# 1-Controller.net
KiCad netlist of a schematic drawn in Altium Designer
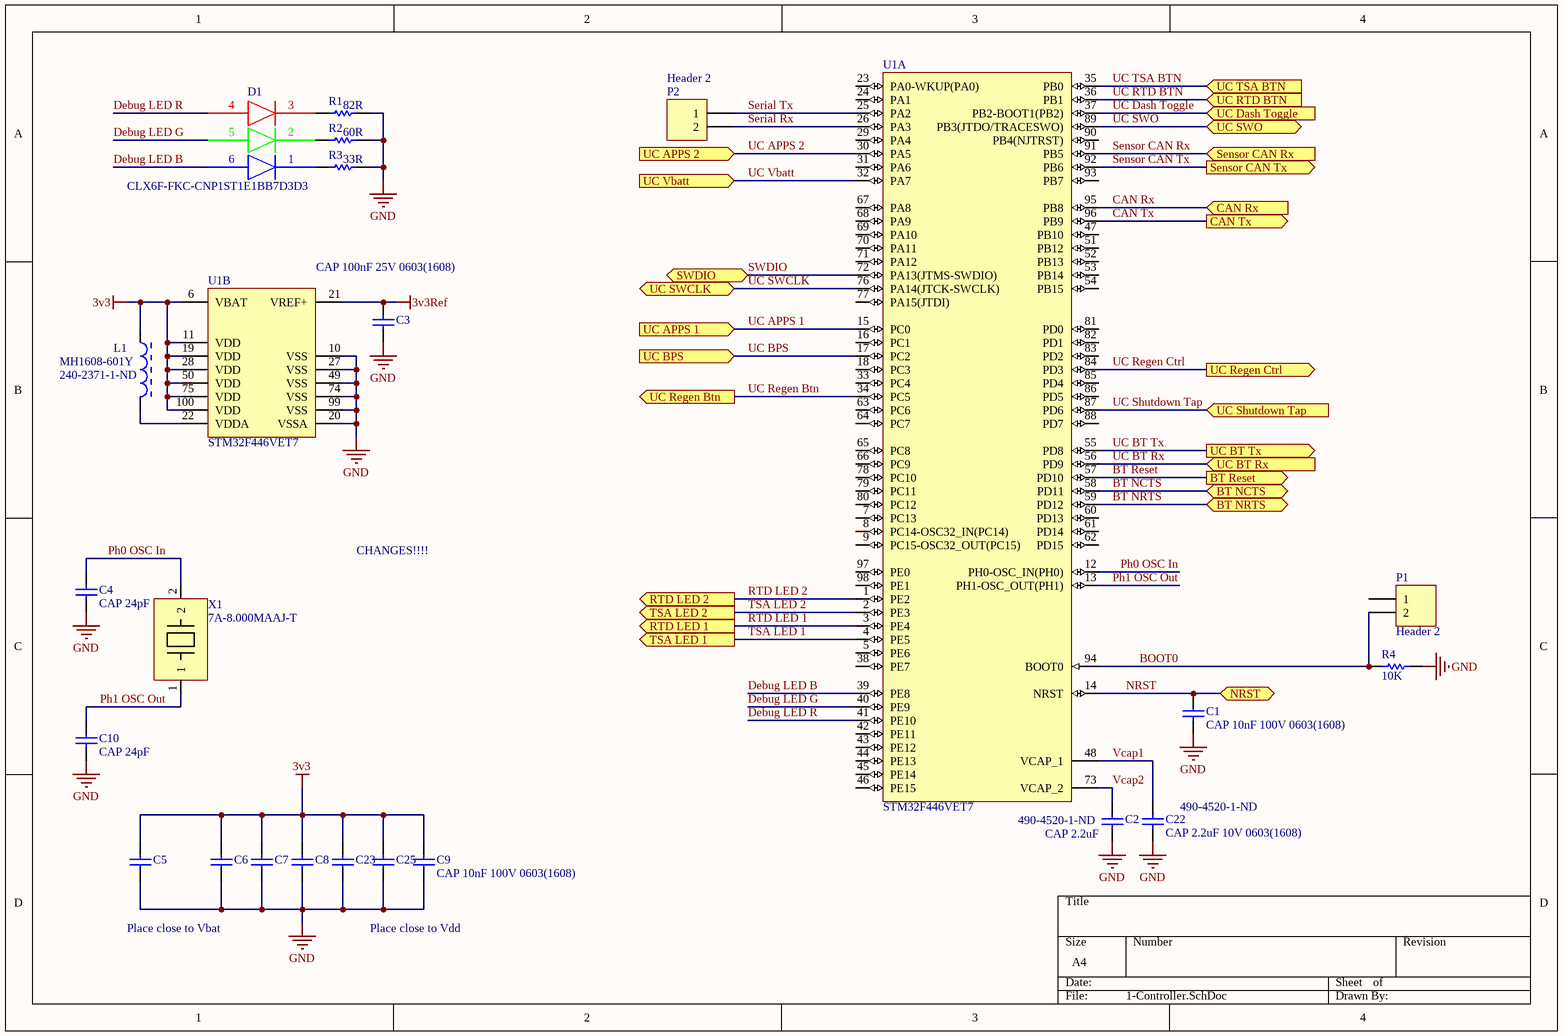
[diagram p0: 1-Controller.SchDoc]

(export (version "E")
  (design (tool "Eeschema 10.0.6"))
  (components
    (comp (ref "C1")
      (value "CAP 10nF 100V 0603(1608)")
      (footprint "CAPC0603(1608)100_M")
      (description "CAP 10nF 100V ±20% 0603 (1608 Metric) Thickness 1mm SMD")
      (fields (field (name "TOLERANCE") "Â±20%"))
      (libsource (lib "Altium Content Vault") (part "CAP"))
    )
    (comp (ref "C2")
      (value "CAP 2.2uF")
      (footprint "CAPC0603(1608)55_N")
      (description "CAP 2.2uF 10V ±10% 0603 (1608 Metric) Thickness 0.55mm SMD")
      (fields (field (name "TOLERANCE") "Â±10%") (field (name "SUPPLIER PART NUMBER 1") "490-4520-1-ND"))
      (libsource (lib "Altium Content Vault") (part "CAP"))
    )
    (comp (ref "C3")
      (value "CAP 100nF 25V 0603(1608)")
      (footprint "CAPC0603(1608)100_N")
      (description "CAP 100nF 25V ±20% 0603 (1608 Metric) Thickness 1mm SMD")
      (fields (field (name "TOLERANCE") "Â±20%"))
      (libsource (lib "Altium Content Vault") (part "CAP"))
    )
    (comp (ref "C4")
      (value "CAP 24pF")
      (footprint "CAPC0603(1608)100_N")
      (description "CAP 24pF 16V ±2% 0603 (1608 Metric) Thickness 1mm SMD")
      (fields (field (name "TOLERANCE") "Â±2%"))
      (libsource (lib "Altium Content Vault") (part "CAP"))
    )
    (comp (ref "C5")
      (value "CAP 10nF 100V 0603(1608)")
      (footprint "CAPC0603(1608)100_M")
      (description "CAP 10nF 100V ±20% 0603 (1608 Metric) Thickness 1mm SMD")
      (fields (field (name "TOLERANCE") "Â±20%"))
      (libsource (lib "Altium Content Vault") (part "CAP"))
    )
    (comp (ref "C6")
      (value "CAP 10nF 100V 0603(1608)")
      (footprint "CAPC0603(1608)100_M")
      (description "CAP 10nF 100V ±20% 0603 (1608 Metric) Thickness 1mm SMD")
      (fields (field (name "TOLERANCE") "Â±20%"))
      (libsource (lib "Altium Content Vault") (part "CAP"))
    )
    (comp (ref "C7")
      (value "CAP 10nF 100V 0603(1608)")
      (footprint "CAPC0603(1608)100_M")
      (description "CAP 10nF 100V ±20% 0603 (1608 Metric) Thickness 1mm SMD")
      (fields (field (name "TOLERANCE") "Â±20%"))
      (libsource (lib "Altium Content Vault") (part "CAP"))
    )
    (comp (ref "C8")
      (value "CAP 10nF 100V 0603(1608)")
      (footprint "CAPC0603(1608)100_M")
      (description "CAP 10nF 100V ±20% 0603 (1608 Metric) Thickness 1mm SMD")
      (fields (field (name "TOLERANCE") "Â±20%"))
      (libsource (lib "Altium Content Vault") (part "CAP"))
    )
    (comp (ref "C9")
      (value "CAP 10nF 100V 0603(1608)")
      (footprint "CAPC0603(1608)100_M")
      (description "CAP 10nF 100V ±20% 0603 (1608 Metric) Thickness 1mm SMD")
      (fields (field (name "TOLERANCE") "Â±20%"))
      (libsource (lib "Altium Content Vault") (part "CAP"))
    )
    (comp (ref "C10")
      (value "CAP 24pF")
      (footprint "CAPC0603(1608)100_N")
      (description "CAP 24pF 16V ±2% 0603 (1608 Metric) Thickness 1mm SMD")
      (fields (field (name "TOLERANCE") "Â±2%"))
      (libsource (lib "Altium Content Vault") (part "CAP"))
    )
    (comp (ref "C22")
      (value "CAP 2.2uF 10V 0603(1608)")
      (footprint "CAPC0603(1608)55_N")
      (description "CAP 2.2uF 10V ±10% 0603 (1608 Metric) Thickness 0.55mm SMD")
      (fields (field (name "TOLERANCE") "Â±10%") (field (name "SUPPLIER PART NUMBER 1") "490-4520-1-ND"))
      (libsource (lib "Altium Content Vault") (part "CAP"))
    )
    (comp (ref "C23")
      (value "CAP 10nF 100V 0603(1608)")
      (footprint "CAPC0603(1608)100_M")
      (description "CAP 10nF 100V ±20% 0603 (1608 Metric) Thickness 1mm SMD")
      (fields (field (name "TOLERANCE") "Â±20%"))
      (libsource (lib "Altium Content Vault") (part "CAP"))
    )
    (comp (ref "C25")
      (value "CAP 10nF 100V 0603(1608)")
      (footprint "CAPC0603(1608)100_M")
      (description "CAP 10nF 100V ±20% 0603 (1608 Metric) Thickness 1mm SMD")
      (fields (field (name "TOLERANCE") "Â±20%"))
      (libsource (lib "Altium Content Vault") (part "CAP"))
    )
    (comp (ref "D1")
      (value "CLX6F-FKC-CNP1ST1E1BB7D3D3")
      (footprint "CLX6C-FKB")
      (libsource (lib "VCB_2019") (part "LED - CLX6F-FKC-CNP1ST1E1BB7D3D3"))
    )
    (comp (ref "L1")
      (value "MH1608-601Y")
      (footprint "BOUR-MH1608_V")
      (description "Chip Bead, 600 Ohm, 1 A, -55 to 125 degC, 2-Pin SMD (0603), RoHS, Tape and Reel")
      (fields (field (name "MANUFACTURER") "Bourns") (field (name "SUPPLIER PART NUMBER 1") "240-2371-1-ND"))
      (libsource (lib "Altium Content Vault") (part "IND-FB-2"))
    )
    (comp (ref "P1")
      (value "Header 2")
      (footprint "HDR1X2")
      (description "Header, 2-Pin")
      (fields (field (name "PUBLISHER") "Altium Limited"))
      (libsource (lib "Miscellaneous Connectors") (part "Header 2"))
    )
    (comp (ref "P2")
      (value "Header 2")
      (footprint "HDR1X2")
      (description "Header, 2-Pin")
      (fields (field (name "PUBLISHER") "Altium Limited"))
      (libsource (lib "") (part "Header 2_1"))
    )
    (comp (ref "R1")
      (value "82R")
      (footprint "RESC0603(1608)_N")
      (description "82R 0.1W 5% 0603 (1608 Metric)  SMD")
      (fields (field (name "TOLERANCE") "5 %") (field (name "POWER") "0.1 W"))
      (libsource (lib "Altium Content Vault") (part "RES"))
    )
    (comp (ref "R2")
      (value "60R")
      (footprint "RESC0603(1608)_N")
      (description "60R4 0.1W 1% 0603 (1608 Metric)  SMD")
      (fields (field (name "TOLERANCE") "1 %") (field (name "POWER") "0.1 W"))
      (libsource (lib "Altium Content Vault") (part "RES"))
    )
    (comp (ref "R3")
      (value "33R")
      (footprint "RESC0603(1608)_N")
      (description "33R 0.1W 5% 0603 (1608 Metric)  SMD")
      (fields (field (name "TOLERANCE") "5 %") (field (name "POWER") "0.1 W"))
      (libsource (lib "Altium Content Vault") (part "RES"))
    )
    (comp (ref "R4")
      (value "10K")
      (footprint "RESC0603(1608)_N")
      (description "10K 0.1W 5% 0603 (1608 Metric)  SMD")
      (fields (field (name "TOLERANCE") "5 %") (field (name "POWER") "0.1 W"))
      (libsource (lib "Altium Content Vault") (part "RES"))
    )
    (comp (ref "U1")
      (value "STM32F446VET7")
      (footprint "STM-LQFP100_L")
      (libsource (lib "Altium Content Vault") (part "MC-ARM-STM32F446-LQFP100"))
    )
    (comp (ref "X1")
      (value "7A-8.000MAAJ-T")
      (footprint "2-SMD, No Lead")
      (fields (field (name "MANUFACTURER") "TXC CORPORATION"))
      (libsource (lib "VCU Library") (part "8MHz crystal, 7A-8.000MAAJ-T"))
    )
  )
  (nets
    (net (code "1") (name "/BOOT0") (class "Default")
      (node (ref "P1") (pin "2") (pinfunction "2_2") (pintype "passive"))
      (node (ref "R4") (pin "1") (pinfunction "1_1") (pintype "passive"))
      (node (ref "U1") (pin "94") (pinfunction "BOOT0_94") (pintype "input"))
    )
    (net (code "2") (name "/BT NCTS") (class "Default")
      (node (ref "U1") (pin "58") (pinfunction "PD11_58") (pintype "bidirectional"))
    )
    (net (code "3") (name "/BT NRTS") (class "Default")
      (node (ref "U1") (pin "59") (pinfunction "PD12_59") (pintype "bidirectional"))
    )
    (net (code "4") (name "/BT Reset") (class "Default")
      (node (ref "U1") (pin "57") (pinfunction "PD10_57") (pintype "bidirectional"))
    )
    (net (code "5") (name "/CAN Rx") (class "Default")
      (node (ref "U1") (pin "95") (pinfunction "PB8_95") (pintype "bidirectional"))
    )
    (net (code "6") (name "/CAN Tx") (class "Default")
      (node (ref "U1") (pin "96") (pinfunction "PB9_96") (pintype "bidirectional"))
    )
    (net (code "7") (name "/Debug LED B") (class "Default")
      (node (ref "D1") (pin "6") (pinfunction "B_6") (pintype "passive"))
      (node (ref "U1") (pin "39") (pinfunction "PE8_39") (pintype "bidirectional"))
    )
    (net (code "8") (name "/Debug LED G") (class "Default")
      (node (ref "D1") (pin "5") (pinfunction "G_5") (pintype "passive"))
      (node (ref "U1") (pin "40") (pinfunction "PE9_40") (pintype "bidirectional"))
    )
    (net (code "9") (name "/Debug LED R") (class "Default")
      (node (ref "D1") (pin "4") (pinfunction "R_4") (pintype "passive"))
      (node (ref "U1") (pin "41") (pinfunction "PE10_41") (pintype "bidirectional"))
    )
    (net (code "10") (name "/NRST") (class "Default")
      (node (ref "C1") (pin "2") (pinfunction "2_2") (pintype "passive"))
      (node (ref "U1") (pin "14") (pinfunction "NRST_14") (pintype "bidirectional"))
    )
    (net (code "11") (name "/Ph0 OSC In") (class "Default")
      (node (ref "C4") (pin "2") (pinfunction "2_2") (pintype "passive"))
      (node (ref "U1") (pin "12") (pinfunction "PH0-OSC_IN(PH0)_12") (pintype "bidirectional"))
      (node (ref "X1") (pin "2") (pinfunction "2_2") (pintype "passive"))
    )
    (net (code "12") (name "/Ph1 OSC Out") (class "Default")
      (node (ref "C10") (pin "2") (pinfunction "2_2") (pintype "passive"))
      (node (ref "U1") (pin "13") (pinfunction "PH1-OSC_OUT(PH1)_13") (pintype "bidirectional"))
      (node (ref "X1") (pin "1") (pinfunction "1_1") (pintype "passive"))
    )
    (net (code "13") (name "/RTD LED 1") (class "Default")
      (node (ref "U1") (pin "3") (pinfunction "PE4_3") (pintype "bidirectional"))
    )
    (net (code "14") (name "/RTD LED 2") (class "Default")
      (node (ref "U1") (pin "1") (pinfunction "PE2_1") (pintype "bidirectional"))
    )
    (net (code "15") (name "/SWDIO") (class "Default")
      (node (ref "U1") (pin "72") (pinfunction "PA13(JTMS-SWDIO)_72") (pintype "bidirectional"))
    )
    (net (code "16") (name "/Sensor CAN Rx") (class "Default")
      (node (ref "U1") (pin "91") (pinfunction "PB5_91") (pintype "bidirectional"))
    )
    (net (code "17") (name "/Sensor CAN Tx") (class "Default")
      (node (ref "U1") (pin "92") (pinfunction "PB6_92") (pintype "bidirectional"))
    )
    (net (code "18") (name "/Serial Rx") (class "Default")
      (node (ref "P2") (pin "2") (pinfunction "2_2") (pintype "passive"))
      (node (ref "U1") (pin "26") (pinfunction "PA3_26") (pintype "bidirectional"))
    )
    (net (code "19") (name "/Serial Tx") (class "Default")
      (node (ref "P2") (pin "1") (pinfunction "1_1") (pintype "passive"))
      (node (ref "U1") (pin "25") (pinfunction "PA2_25") (pintype "bidirectional"))
    )
    (net (code "20") (name "/TSA LED 1") (class "Default")
      (node (ref "U1") (pin "4") (pinfunction "PE5_4") (pintype "bidirectional"))
    )
    (net (code "21") (name "/TSA LED 2") (class "Default")
      (node (ref "U1") (pin "2") (pinfunction "PE3_2") (pintype "bidirectional"))
    )
    (net (code "22") (name "/UC APPS 1") (class "Default")
      (node (ref "U1") (pin "15") (pinfunction "PC0_15") (pintype "bidirectional"))
    )
    (net (code "23") (name "/UC APPS 2") (class "Default")
      (node (ref "U1") (pin "30") (pinfunction "PA5_30") (pintype "bidirectional"))
    )
    (net (code "24") (name "/UC BPS") (class "Default")
      (node (ref "U1") (pin "17") (pinfunction "PC2_17") (pintype "bidirectional"))
    )
    (net (code "25") (name "/UC BT Rx") (class "Default")
      (node (ref "U1") (pin "56") (pinfunction "PD9_56") (pintype "bidirectional"))
    )
    (net (code "26") (name "/UC BT Tx") (class "Default")
      (node (ref "U1") (pin "55") (pinfunction "PD8_55") (pintype "bidirectional"))
    )
    (net (code "27") (name "/UC Dash Toggle") (class "Default")
      (node (ref "U1") (pin "37") (pinfunction "PB2-BOOT1(PB2)_37") (pintype "bidirectional"))
    )
    (net (code "28") (name "/UC RTD BTN") (class "Default")
      (node (ref "U1") (pin "36") (pinfunction "PB1_36") (pintype "bidirectional"))
    )
    (net (code "29") (name "/UC Regen Btn") (class "Default")
      (node (ref "U1") (pin "34") (pinfunction "PC5_34") (pintype "bidirectional"))
    )
    (net (code "30") (name "/UC Regen Ctrl") (class "Default")
      (node (ref "U1") (pin "84") (pinfunction "PD3_84") (pintype "bidirectional"))
    )
    (net (code "31") (name "/UC SWCLK") (class "Default")
      (node (ref "U1") (pin "76") (pinfunction "PA14(JTCK-SWCLK)_76") (pintype "bidirectional"))
    )
    (net (code "32") (name "/UC SWO") (class "Default")
      (node (ref "U1") (pin "89") (pinfunction "PB3(JTDO/TRACESWO)_89") (pintype "bidirectional"))
    )
    (net (code "33") (name "/UC Shutdown Tap") (class "Default")
      (node (ref "U1") (pin "87") (pinfunction "PD6_87") (pintype "bidirectional"))
    )
    (net (code "34") (name "/UC TSA BTN") (class "Default")
      (node (ref "U1") (pin "35") (pinfunction "PB0_35") (pintype "bidirectional"))
    )
    (net (code "35") (name "/UC Vbatt") (class "Default")
      (node (ref "U1") (pin "32") (pinfunction "PA7_32") (pintype "bidirectional"))
    )
    (net (code "36") (name "/Vcap1") (class "Default")
      (node (ref "C22") (pin "2") (pinfunction "2_2") (pintype "passive"))
      (node (ref "U1") (pin "48") (pinfunction "VCAP_1_48") (pintype "passive"))
    )
    (net (code "37") (name "/Vcap2") (class "Default")
      (node (ref "C2") (pin "2") (pinfunction "2_2") (pintype "passive"))
      (node (ref "U1") (pin "73") (pinfunction "VCAP_2_73") (pintype "passive"))
    )
    (net (code "38") (name "3v3") (class "Default")
      (node (ref "C23") (pin "2") (pinfunction "2_2") (pintype "passive"))
      (node (ref "C25") (pin "2") (pinfunction "2_2") (pintype "passive"))
      (node (ref "C5") (pin "2") (pinfunction "2_2") (pintype "passive"))
      (node (ref "C6") (pin "2") (pinfunction "2_2") (pintype "passive"))
      (node (ref "C7") (pin "2") (pinfunction "2_2") (pintype "passive"))
      (node (ref "C8") (pin "2") (pinfunction "2_2") (pintype "passive"))
      (node (ref "C9") (pin "2") (pinfunction "2_2") (pintype "passive"))
      (node (ref "L1") (pin "1") (pinfunction "1_1") (pintype "passive"))
      (node (ref "U1") (pin "100") (pinfunction "VDD_100") (pintype "power_in"))
      (node (ref "U1") (pin "11") (pinfunction "VDD_11") (pintype "power_in"))
      (node (ref "U1") (pin "19") (pinfunction "VDD_19") (pintype "power_in"))
      (node (ref "U1") (pin "28") (pinfunction "VDD_28") (pintype "power_in"))
      (node (ref "U1") (pin "50") (pinfunction "VDD_50") (pintype "power_in"))
      (node (ref "U1") (pin "6") (pinfunction "VBAT_6") (pintype "power_in"))
      (node (ref "U1") (pin "75") (pinfunction "VDD_75") (pintype "power_in"))
    )
    (net (code "39") (name "3v3Ref") (class "Default")
      (node (ref "C3") (pin "2") (pinfunction "2_2") (pintype "passive"))
      (node (ref "U1") (pin "21") (pinfunction "VREF+_21") (pintype "power_in"))
    )
    (net (code "40") (name "GND") (class "Default")
      (node (ref "C1") (pin "1") (pinfunction "1_1") (pintype "passive"))
      (node (ref "C10") (pin "1") (pinfunction "1_1") (pintype "passive"))
      (node (ref "C2") (pin "1") (pinfunction "1_1") (pintype "passive"))
      (node (ref "C22") (pin "1") (pinfunction "1_1") (pintype "passive"))
      (node (ref "C23") (pin "1") (pinfunction "1_1") (pintype "passive"))
      (node (ref "C25") (pin "1") (pinfunction "1_1") (pintype "passive"))
      (node (ref "C3") (pin "1") (pinfunction "1_1") (pintype "passive"))
      (node (ref "C4") (pin "1") (pinfunction "1_1") (pintype "passive"))
      (node (ref "C5") (pin "1") (pinfunction "1_1") (pintype "passive"))
      (node (ref "C6") (pin "1") (pinfunction "1_1") (pintype "passive"))
      (node (ref "C7") (pin "1") (pinfunction "1_1") (pintype "passive"))
      (node (ref "C8") (pin "1") (pinfunction "1_1") (pintype "passive"))
      (node (ref "C9") (pin "1") (pinfunction "1_1") (pintype "passive"))
      (node (ref "R1") (pin "2") (pinfunction "2_2") (pintype "passive"))
      (node (ref "R2") (pin "2") (pinfunction "2_2") (pintype "passive"))
      (node (ref "R3") (pin "2") (pinfunction "2_2") (pintype "passive"))
      (node (ref "R4") (pin "2") (pinfunction "2_2") (pintype "passive"))
      (node (ref "U1") (pin "10") (pinfunction "VSS_10") (pintype "power_in"))
      (node (ref "U1") (pin "20") (pinfunction "VSSA_20") (pintype "power_in"))
      (node (ref "U1") (pin "27") (pinfunction "VSS_27") (pintype "power_in"))
      (node (ref "U1") (pin "49") (pinfunction "VSS_49") (pintype "power_in"))
      (node (ref "U1") (pin "74") (pinfunction "VSS_74") (pintype "power_in"))
      (node (ref "U1") (pin "99") (pinfunction "VSS_99") (pintype "power_in"))
    )
    (net (code "41") (name "Net-(D1-B-Pad1)") (class "Default")
      (node (ref "D1") (pin "1") (pinfunction "B_1") (pintype "passive"))
      (node (ref "R3") (pin "1") (pinfunction "1_1") (pintype "passive"))
    )
    (net (code "42") (name "Net-(D1-G-Pad2)") (class "Default")
      (node (ref "D1") (pin "2") (pinfunction "G_2") (pintype "passive"))
      (node (ref "R2") (pin "1") (pinfunction "1_1") (pintype "passive"))
    )
    (net (code "43") (name "Net-(D1-R-Pad3)") (class "Default")
      (node (ref "D1") (pin "3") (pinfunction "R_3") (pintype "passive"))
      (node (ref "R1") (pin "1") (pinfunction "1_1") (pintype "passive"))
    )
    (net (code "44") (name "Net-(U1B-VDDA)") (class "Default")
      (node (ref "L1") (pin "2") (pinfunction "2_2") (pintype "passive"))
      (node (ref "U1") (pin "22") (pinfunction "VDDA_22") (pintype "power_in"))
    )
    (net (code "45") (name "unconnected-(P1-Pad1)") (class "Default")
      (node (ref "P1") (pin "1") (pinfunction "1_1") (pintype "passive"))
    )
    (net (code "46") (name "unconnected-(U1A-PA0-WKUP(PA0)-Pad23)") (class "Default")
      (node (ref "U1") (pin "23") (pinfunction "PA0-WKUP(PA0)_23") (pintype "bidirectional"))
    )
    (net (code "47") (name "unconnected-(U1A-PA1-Pad24)") (class "Default")
      (node (ref "U1") (pin "24") (pinfunction "PA1_24") (pintype "bidirectional"))
    )
    (net (code "48") (name "unconnected-(U1A-PA4-Pad29)") (class "Default")
      (node (ref "U1") (pin "29") (pinfunction "PA4_29") (pintype "bidirectional"))
    )
    (net (code "49") (name "unconnected-(U1A-PA6-Pad31)") (class "Default")
      (node (ref "U1") (pin "31") (pinfunction "PA6_31") (pintype "bidirectional"))
    )
    (net (code "50") (name "unconnected-(U1A-PA8-Pad67)") (class "Default")
      (node (ref "U1") (pin "67") (pinfunction "PA8_67") (pintype "bidirectional"))
    )
    (net (code "51") (name "unconnected-(U1A-PA9-Pad68)") (class "Default")
      (node (ref "U1") (pin "68") (pinfunction "PA9_68") (pintype "bidirectional"))
    )
    (net (code "52") (name "unconnected-(U1A-PA10-Pad69)") (class "Default")
      (node (ref "U1") (pin "69") (pinfunction "PA10_69") (pintype "bidirectional"))
    )
    (net (code "53") (name "unconnected-(U1A-PA11-Pad70)") (class "Default")
      (node (ref "U1") (pin "70") (pinfunction "PA11_70") (pintype "bidirectional"))
    )
    (net (code "54") (name "unconnected-(U1A-PA12-Pad71)") (class "Default")
      (node (ref "U1") (pin "71") (pinfunction "PA12_71") (pintype "bidirectional"))
    )
    (net (code "55") (name "unconnected-(U1A-PA15(JTDI)-Pad77)") (class "Default")
      (node (ref "U1") (pin "77") (pinfunction "PA15(JTDI)_77") (pintype "bidirectional"))
    )
    (net (code "56") (name "unconnected-(U1A-PB4(NJTRST)-Pad90)") (class "Default")
      (node (ref "U1") (pin "90") (pinfunction "PB4(NJTRST)_90") (pintype "bidirectional"))
    )
    (net (code "57") (name "unconnected-(U1A-PB7-Pad93)") (class "Default")
      (node (ref "U1") (pin "93") (pinfunction "PB7_93") (pintype "bidirectional"))
    )
    (net (code "58") (name "unconnected-(U1A-PB10-Pad47)") (class "Default")
      (node (ref "U1") (pin "47") (pinfunction "PB10_47") (pintype "bidirectional"))
    )
    (net (code "59") (name "unconnected-(U1A-PB12-Pad51)") (class "Default")
      (node (ref "U1") (pin "51") (pinfunction "PB12_51") (pintype "bidirectional"))
    )
    (net (code "60") (name "unconnected-(U1A-PB13-Pad52)") (class "Default")
      (node (ref "U1") (pin "52") (pinfunction "PB13_52") (pintype "bidirectional"))
    )
    (net (code "61") (name "unconnected-(U1A-PB14-Pad53)") (class "Default")
      (node (ref "U1") (pin "53") (pinfunction "PB14_53") (pintype "bidirectional"))
    )
    (net (code "62") (name "unconnected-(U1A-PB15-Pad54)") (class "Default")
      (node (ref "U1") (pin "54") (pinfunction "PB15_54") (pintype "bidirectional"))
    )
    (net (code "63") (name "unconnected-(U1A-PC1-Pad16)") (class "Default")
      (node (ref "U1") (pin "16") (pinfunction "PC1_16") (pintype "bidirectional"))
    )
    (net (code "64") (name "unconnected-(U1A-PC3-Pad18)") (class "Default")
      (node (ref "U1") (pin "18") (pinfunction "PC3_18") (pintype "bidirectional"))
    )
    (net (code "65") (name "unconnected-(U1A-PC4-Pad33)") (class "Default")
      (node (ref "U1") (pin "33") (pinfunction "PC4_33") (pintype "bidirectional"))
    )
    (net (code "66") (name "unconnected-(U1A-PC6-Pad63)") (class "Default")
      (node (ref "U1") (pin "63") (pinfunction "PC6_63") (pintype "bidirectional"))
    )
    (net (code "67") (name "unconnected-(U1A-PC7-Pad64)") (class "Default")
      (node (ref "U1") (pin "64") (pinfunction "PC7_64") (pintype "bidirectional"))
    )
    (net (code "68") (name "unconnected-(U1A-PC8-Pad65)") (class "Default")
      (node (ref "U1") (pin "65") (pinfunction "PC8_65") (pintype "bidirectional"))
    )
    (net (code "69") (name "unconnected-(U1A-PC9-Pad66)") (class "Default")
      (node (ref "U1") (pin "66") (pinfunction "PC9_66") (pintype "bidirectional"))
    )
    (net (code "70") (name "unconnected-(U1A-PC10-Pad78)") (class "Default")
      (node (ref "U1") (pin "78") (pinfunction "PC10_78") (pintype "bidirectional"))
    )
    (net (code "71") (name "unconnected-(U1A-PC11-Pad79)") (class "Default")
      (node (ref "U1") (pin "79") (pinfunction "PC11_79") (pintype "bidirectional"))
    )
    (net (code "72") (name "unconnected-(U1A-PC12-Pad80)") (class "Default")
      (node (ref "U1") (pin "80") (pinfunction "PC12_80") (pintype "bidirectional"))
    )
    (net (code "73") (name "unconnected-(U1A-PC13-Pad7)") (class "Default")
      (node (ref "U1") (pin "7") (pinfunction "PC13_7") (pintype "bidirectional"))
    )
    (net (code "74") (name "unconnected-(U1A-PC14-OSC32_IN(PC14)-Pad8)") (class "Default")
      (node (ref "U1") (pin "8") (pinfunction "PC14-OSC32_IN(PC14)_8") (pintype "bidirectional"))
    )
    (net (code "75") (name "unconnected-(U1A-PC15-OSC32_OUT(PC15)-Pad9)") (class "Default")
      (node (ref "U1") (pin "9") (pinfunction "PC15-OSC32_OUT(PC15)_9") (pintype "bidirectional"))
    )
    (net (code "76") (name "unconnected-(U1A-PD0-Pad81)") (class "Default")
      (node (ref "U1") (pin "81") (pinfunction "PD0_81") (pintype "bidirectional"))
    )
    (net (code "77") (name "unconnected-(U1A-PD1-Pad82)") (class "Default")
      (node (ref "U1") (pin "82") (pinfunction "PD1_82") (pintype "bidirectional"))
    )
    (net (code "78") (name "unconnected-(U1A-PD2-Pad83)") (class "Default")
      (node (ref "U1") (pin "83") (pinfunction "PD2_83") (pintype "bidirectional"))
    )
    (net (code "79") (name "unconnected-(U1A-PD4-Pad85)") (class "Default")
      (node (ref "U1") (pin "85") (pinfunction "PD4_85") (pintype "bidirectional"))
    )
    (net (code "80") (name "unconnected-(U1A-PD5-Pad86)") (class "Default")
      (node (ref "U1") (pin "86") (pinfunction "PD5_86") (pintype "bidirectional"))
    )
    (net (code "81") (name "unconnected-(U1A-PD7-Pad88)") (class "Default")
      (node (ref "U1") (pin "88") (pinfunction "PD7_88") (pintype "bidirectional"))
    )
    (net (code "82") (name "unconnected-(U1A-PD13-Pad60)") (class "Default")
      (node (ref "U1") (pin "60") (pinfunction "PD13_60") (pintype "bidirectional"))
    )
    (net (code "83") (name "unconnected-(U1A-PD14-Pad61)") (class "Default")
      (node (ref "U1") (pin "61") (pinfunction "PD14_61") (pintype "bidirectional"))
    )
    (net (code "84") (name "unconnected-(U1A-PD15-Pad62)") (class "Default")
      (node (ref "U1") (pin "62") (pinfunction "PD15_62") (pintype "bidirectional"))
    )
    (net (code "85") (name "unconnected-(U1A-PE0-Pad97)") (class "Default")
      (node (ref "U1") (pin "97") (pinfunction "PE0_97") (pintype "bidirectional"))
    )
    (net (code "86") (name "unconnected-(U1A-PE1-Pad98)") (class "Default")
      (node (ref "U1") (pin "98") (pinfunction "PE1_98") (pintype "bidirectional"))
    )
    (net (code "87") (name "unconnected-(U1A-PE6-Pad5)") (class "Default")
      (node (ref "U1") (pin "5") (pinfunction "PE6_5") (pintype "bidirectional"))
    )
    (net (code "88") (name "unconnected-(U1A-PE7-Pad38)") (class "Default")
      (node (ref "U1") (pin "38") (pinfunction "PE7_38") (pintype "bidirectional"))
    )
    (net (code "89") (name "unconnected-(U1A-PE11-Pad42)") (class "Default")
      (node (ref "U1") (pin "42") (pinfunction "PE11_42") (pintype "bidirectional"))
    )
    (net (code "90") (name "unconnected-(U1A-PE12-Pad43)") (class "Default")
      (node (ref "U1") (pin "43") (pinfunction "PE12_43") (pintype "bidirectional"))
    )
    (net (code "91") (name "unconnected-(U1A-PE13-Pad44)") (class "Default")
      (node (ref "U1") (pin "44") (pinfunction "PE13_44") (pintype "bidirectional"))
    )
    (net (code "92") (name "unconnected-(U1A-PE14-Pad45)") (class "Default")
      (node (ref "U1") (pin "45") (pinfunction "PE14_45") (pintype "bidirectional"))
    )
    (net (code "93") (name "unconnected-(U1A-PE15-Pad46)") (class "Default")
      (node (ref "U1") (pin "46") (pinfunction "PE15_46") (pintype "bidirectional"))
    )
  )
)
